# Guide_laser.net
KiCad netlist of a schematic drawn in Altium Designer
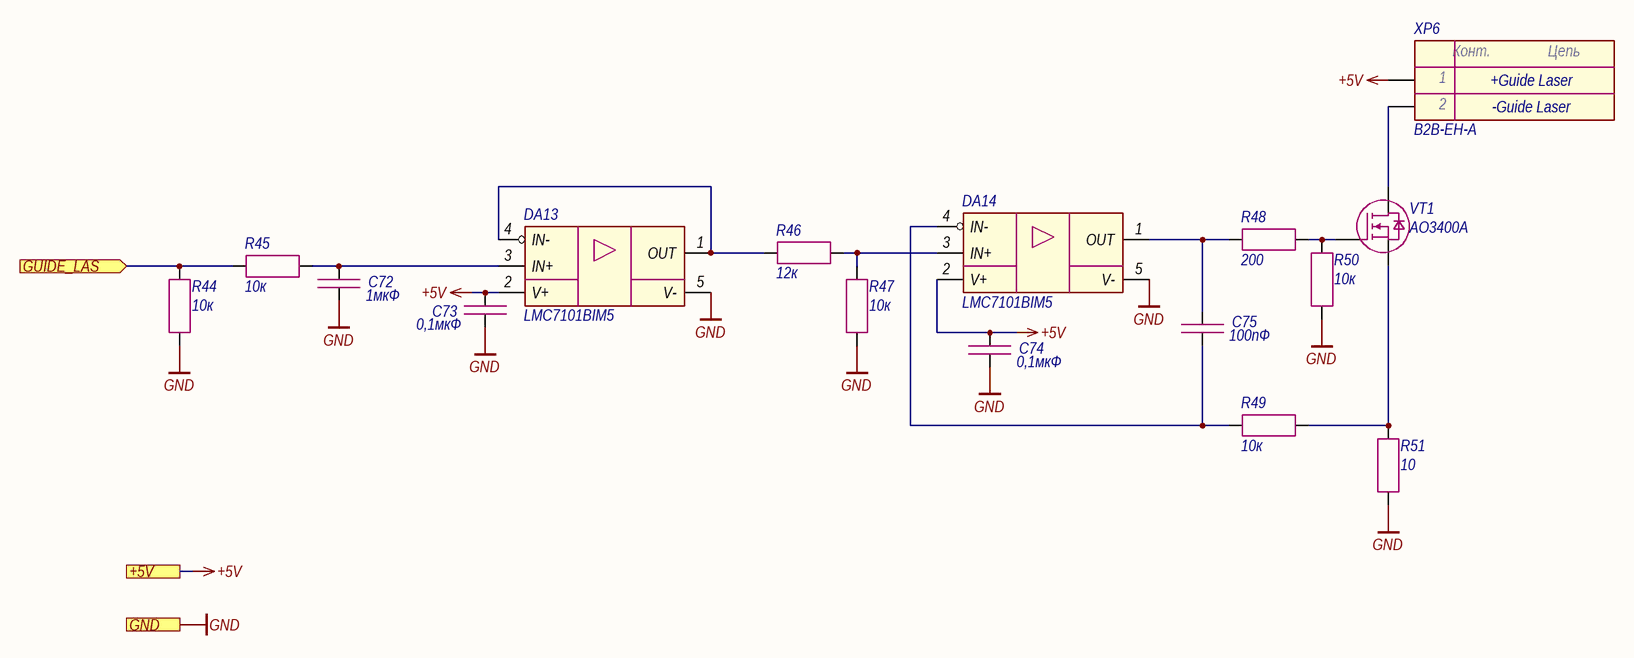
[diagram p0: Guide_laser.SchDoc]

(export (version "E")
  (design (tool "Eeschema 10.0.6"))
  (components
    (comp (ref "C72")
      (value "1мкФ")
      (footprint "Pcb_library:CAP_0603")
      (fields (field (name "MANUFACTURER") "Murata"))
      (libsource (lib "Schem_library") (part "Capacitor"))
    )
    (comp (ref "C73")
      (value "0,1мкФ")
      (footprint "Pcb_library:CAP_0603")
      (fields (field (name "MANUFACTURER") "Murata"))
      (libsource (lib "Schem_library") (part "Capacitor"))
    )
    (comp (ref "C74")
      (value "0,1мкФ")
      (footprint "Pcb_library:CAP_0603")
      (fields (field (name "MANUFACTURER") "Murata"))
      (libsource (lib "Schem_library") (part "Capacitor"))
    )
    (comp (ref "C75")
      (value "100пФ")
      (footprint "Pcb_library:CAP_0603")
      (fields (field (name "MANUFACTURER") "Murata"))
      (libsource (lib "Schem_library") (part "Capacitor"))
    )
    (comp (ref "DA13")
      (value "LMC7101BIM5")
      (footprint "Pcb_library:SOT-23-5")
      (fields (field (name "MANUFACTURER") "Texas Instruments"))
      (libsource (lib "Schem_library") (part "LMC7101"))
    )
    (comp (ref "DA14")
      (value "LMC7101BIM5")
      (footprint "Pcb_library:SOT-23-5")
      (fields (field (name "MANUFACTURER") "Texas Instruments"))
      (libsource (lib "Schem_library") (part "LMC7101"))
    )
    (comp (ref "R44")
      (value "10к")
      (footprint "Pcb_library:RES_0603")
      (fields (field (name "MANUFACTURER") "Yageo"))
      (libsource (lib "Schem_library") (part "Resistor"))
    )
    (comp (ref "R45")
      (value "10к")
      (footprint "Pcb_library:RES_0603")
      (fields (field (name "MANUFACTURER") "Yageo"))
      (libsource (lib "Schem_library") (part "Resistor"))
    )
    (comp (ref "R46")
      (value "12к")
      (footprint "Pcb_library:RES_0603")
      (fields (field (name "MANUFACTURER") "Yageo"))
      (libsource (lib "Schem_library") (part "Resistor"))
    )
    (comp (ref "R47")
      (value "10к")
      (footprint "Pcb_library:RES_0603")
      (fields (field (name "MANUFACTURER") "Yageo"))
      (libsource (lib "Schem_library") (part "Resistor"))
    )
    (comp (ref "R48")
      (value "200")
      (footprint "Pcb_library:RES_0603")
      (fields (field (name "MANUFACTURER") "Yageo"))
      (libsource (lib "Schem_library") (part "Resistor"))
    )
    (comp (ref "R49")
      (value "10к")
      (footprint "Pcb_library:RES_0603")
      (fields (field (name "MANUFACTURER") "Yageo"))
      (libsource (lib "Schem_library") (part "Resistor"))
    )
    (comp (ref "R50")
      (value "10к")
      (footprint "Pcb_library:RES_0603")
      (fields (field (name "MANUFACTURER") "Yageo"))
      (libsource (lib "Schem_library") (part "Resistor"))
    )
    (comp (ref "R51")
      (value "10")
      (footprint "Pcb_library:RES_1210")
      (fields (field (name "MANUFACTURER") "Yageo"))
      (libsource (lib "Schem_library") (part "Resistor"))
    )
    (comp (ref "VT1")
      (value "AO3400A")
      (footprint "Pcb_library:SOT-23-3")
      (fields (field (name "MANUFACTURER") "UMW"))
      (libsource (lib "Schem_library") (part "MOSFET N-channel"))
    )
    (comp (ref "XP6")
      (value "B2B-EH-A")
      (footprint "Pcb_library:B2B-EH-A")
      (fields (field (name "MANUFACTURER") "JST"))
      (libsource (lib "Schem_library") (part "Connector-2"))
    )
  )
  (nets
    (net (code "1") (name "+5V") (class "Default")
      (node (ref "C73") (pin "1") (pinfunction "1_1") (pintype "passive"))
      (node (ref "C74") (pin "1") (pinfunction "1_1") (pintype "passive"))
      (node (ref "DA13") (pin "2") (pinfunction "V+_2") (pintype "passive"))
      (node (ref "DA14") (pin "2") (pinfunction "V+_2") (pintype "passive"))
      (node (ref "XP6") (pin "1") (pintype "passive"))
    )
    (net (code "2") (name "/GUIDE_LAS") (class "Default")
      (node (ref "R44") (pin "2") (pinfunction "2_2") (pintype "passive"))
      (node (ref "R45") (pin "1") (pinfunction "1_1") (pintype "passive"))
    )
    (net (code "3") (name "GND") (class "Default")
      (node (ref "C72") (pin "2") (pinfunction "2_2") (pintype "passive"))
      (node (ref "C73") (pin "2") (pinfunction "2_2") (pintype "passive"))
      (node (ref "C74") (pin "2") (pinfunction "2_2") (pintype "passive"))
      (node (ref "DA13") (pin "5") (pinfunction "V-_5") (pintype "passive"))
      (node (ref "DA14") (pin "5") (pinfunction "V-_5") (pintype "passive"))
      (node (ref "R44") (pin "1") (pinfunction "1_1") (pintype "passive"))
      (node (ref "R47") (pin "2") (pinfunction "2_2") (pintype "passive"))
      (node (ref "R50") (pin "1") (pinfunction "1_1") (pintype "passive"))
      (node (ref "R51") (pin "1") (pinfunction "1_1") (pintype "passive"))
    )
    (net (code "4") (name "Net-(DA13-IN+)") (class "Default")
      (node (ref "C72") (pin "1") (pinfunction "1_1") (pintype "passive"))
      (node (ref "DA13") (pin "3") (pinfunction "IN+_3") (pintype "passive"))
      (node (ref "R45") (pin "2") (pinfunction "2_2") (pintype "passive"))
    )
    (net (code "5") (name "Net-(DA13-IN-)") (class "Default")
      (node (ref "DA13") (pin "1") (pinfunction "OUT_1") (pintype "passive"))
      (node (ref "DA13") (pin "4") (pinfunction "IN-_4") (pintype "passive"))
      (node (ref "R46") (pin "1") (pinfunction "1_1") (pintype "passive"))
    )
    (net (code "6") (name "Net-(DA14-IN+)") (class "Default")
      (node (ref "DA14") (pin "3") (pinfunction "IN+_3") (pintype "passive"))
      (node (ref "R46") (pin "2") (pinfunction "2_2") (pintype "passive"))
      (node (ref "R47") (pin "1") (pinfunction "1_1") (pintype "passive"))
    )
    (net (code "7") (name "Net-(DA14-IN-)") (class "Default")
      (node (ref "C75") (pin "2") (pinfunction "2_2") (pintype "passive"))
      (node (ref "DA14") (pin "4") (pinfunction "IN-_4") (pintype "passive"))
      (node (ref "R49") (pin "1") (pinfunction "1_1") (pintype "passive"))
    )
    (net (code "8") (name "Net-(DA14-OUT)") (class "Default")
      (node (ref "C75") (pin "1") (pinfunction "1_1") (pintype "passive"))
      (node (ref "DA14") (pin "1") (pinfunction "OUT_1") (pintype "passive"))
      (node (ref "R48") (pin "1") (pinfunction "1_1") (pintype "passive"))
    )
    (net (code "9") (name "Net-(VT1-D)") (class "Default")
      (node (ref "VT1") (pin "3") (pinfunction "D_3") (pintype "passive"))
      (node (ref "XP6") (pin "2") (pintype "passive"))
    )
    (net (code "10") (name "Net-(VT1-G)") (class "Default")
      (node (ref "R48") (pin "2") (pinfunction "2_2") (pintype "passive"))
      (node (ref "R50") (pin "2") (pinfunction "2_2") (pintype "passive"))
      (node (ref "VT1") (pin "1") (pinfunction "G_1") (pintype "passive"))
    )
    (net (code "11") (name "Net-(VT1-S)") (class "Default")
      (node (ref "R49") (pin "2") (pinfunction "2_2") (pintype "passive"))
      (node (ref "R51") (pin "2") (pinfunction "2_2") (pintype "passive"))
      (node (ref "VT1") (pin "2") (pinfunction "S_2") (pintype "passive"))
    )
  )
)
